# Inputbuffer_Equalizer.net
KiCad netlist of a schematic drawn in Altium Designer
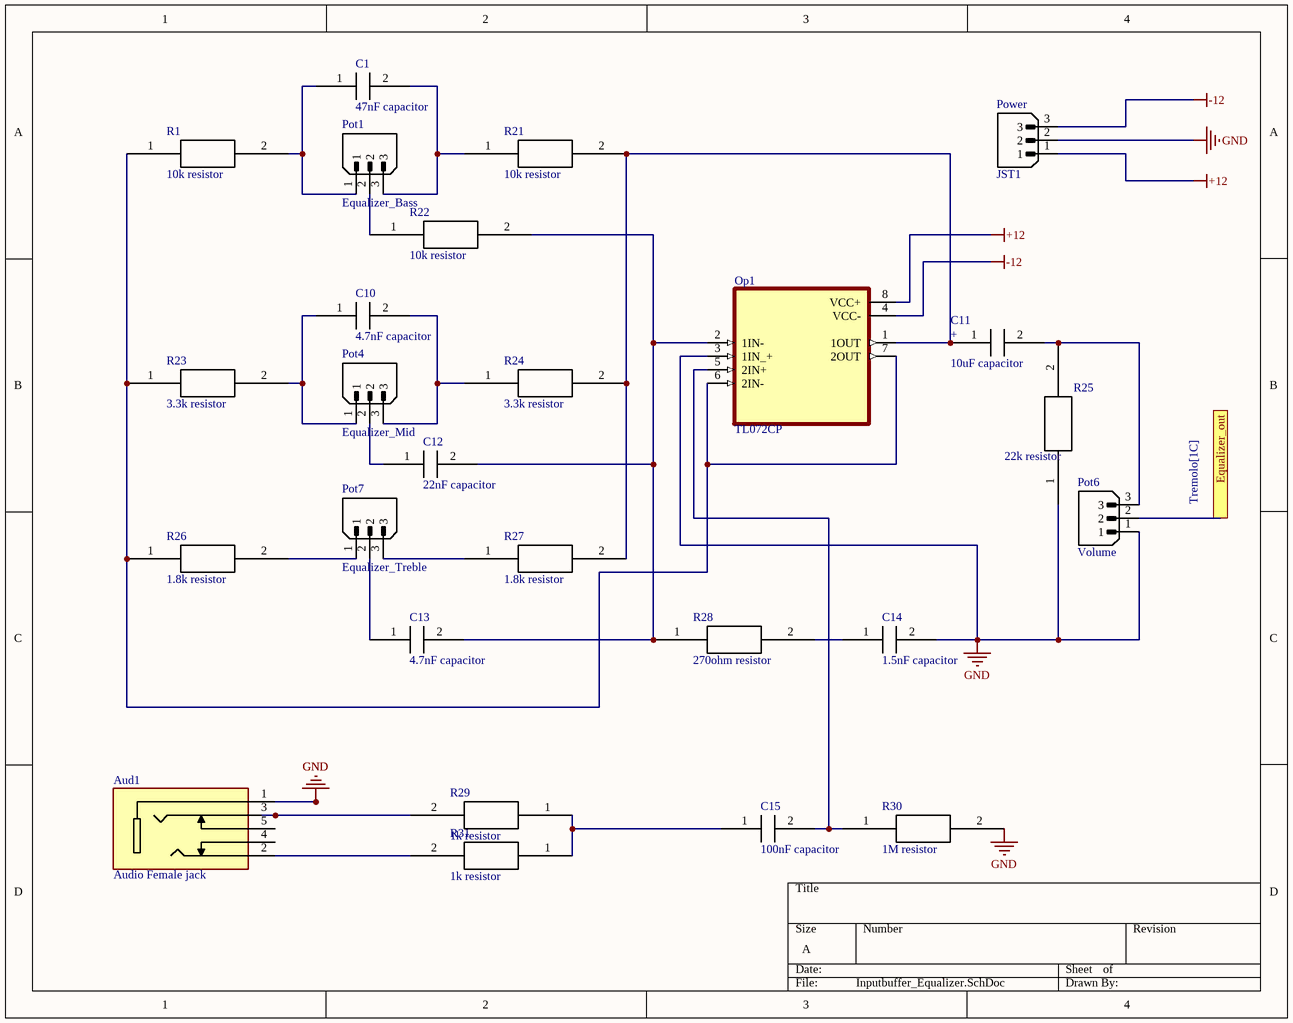
[diagram p0: Inputbuffer_Equalizer.SchDoc]

(export (version "E")
  (design (tool "Eeschema 10.0.6"))
  (components
    (comp (ref "Aud1")
      (value "Audio Female jack")
      (footprint "Audio Female Jack")
      (libsource (lib "Analog_Project_Schlib") (part "Audio Female jack"))
    )
    (comp (ref "C1")
      (value "47nF capacitor")
      (footprint "47nF")
      (libsource (lib "Analog_Project_Schlib") (part "47nF capacitor"))
    )
    (comp (ref "C10")
      (value "4.7nF capacitor")
      (footprint "4.7nF")
      (libsource (lib "Analog_Project_Schlib") (part "4.7nF capacitor"))
    )
    (comp (ref "C11")
      (value "10uF capacitor")
      (footprint "10uF")
      (libsource (lib "Analog_Project_Schlib") (part "10uF capacitor"))
    )
    (comp (ref "C12")
      (value "22nF capacitor")
      (footprint "22nF")
      (libsource (lib "Analog_Project_Schlib") (part "22nF capacitor"))
    )
    (comp (ref "C13")
      (value "4.7nF capacitor")
      (footprint "4.7nF")
      (libsource (lib "Analog_Project_Schlib") (part "4.7nF capacitor"))
    )
    (comp (ref "C14")
      (value "1.5nF capacitor")
      (footprint "1.5nF")
      (libsource (lib "Analog_Project_Schlib") (part "1.5nF capacitor"))
    )
    (comp (ref "C15")
      (value "100nF capacitor")
      (footprint "100nF")
      (libsource (lib "Analog_Project_Schlib") (part "100nF capacitor"))
    )
    (comp (ref "JST1")
      (value "Power")
      (footprint "3pin_jst")
      (libsource (lib "Analog_Project_Schlib") (part "3pin_jst"))
    )
    (comp (ref "Op1")
      (value "TL072CP")
      (footprint "TL072CP")
      (libsource (lib "Analog_Project_Schlib") (part "TL072CP"))
    )
    (comp (ref "Pot1")
      (value "Equalizer_Bass")
      (footprint "3pin_jst")
      (libsource (lib "") (part "3pin_jst_1"))
    )
    (comp (ref "Pot4")
      (value "Equalizer_Mid")
      (footprint "3pin_jst")
      (libsource (lib "") (part "3pin_jst_1"))
    )
    (comp (ref "Pot6")
      (value "Volume")
      (footprint "3pin_jst")
      (libsource (lib "Analog_Project_Schlib") (part "3pin_jst"))
    )
    (comp (ref "Pot7")
      (value "Equalizer_Treble")
      (footprint "3pin_jst")
      (libsource (lib "") (part "3pin_jst_1"))
    )
    (comp (ref "R1")
      (value "10k resistor")
      (footprint "10k")
      (libsource (lib "Analog_Project_Schlib") (part "10k resistor"))
    )
    (comp (ref "R21")
      (value "10k resistor")
      (footprint "10k")
      (libsource (lib "Analog_Project_Schlib") (part "10k resistor"))
    )
    (comp (ref "R22")
      (value "10k resistor")
      (footprint "10k")
      (libsource (lib "Analog_Project_Schlib") (part "10k resistor"))
    )
    (comp (ref "R23")
      (value "3.3k resistor")
      (footprint "3.3k")
      (libsource (lib "Analog_Project_Schlib") (part "3.3k resistor"))
    )
    (comp (ref "R24")
      (value "3.3k resistor")
      (footprint "3.3k")
      (libsource (lib "Analog_Project_Schlib") (part "3.3k resistor"))
    )
    (comp (ref "R25")
      (value "22k resistor")
      (footprint "22k")
      (libsource (lib "Analog_Project_Schlib") (part "22k resistor"))
    )
    (comp (ref "R26")
      (value "1.8k resistor")
      (footprint "1.8k")
      (libsource (lib "Analog_Project_Schlib") (part "1.8k resistor"))
    )
    (comp (ref "R27")
      (value "1.8k resistor")
      (footprint "1.8k")
      (libsource (lib "Analog_Project_Schlib") (part "1.8k resistor"))
    )
    (comp (ref "R28")
      (value "270ohm resistor")
      (footprint "270")
      (libsource (lib "Analog_Project_Schlib") (part "270ohm resistor"))
    )
    (comp (ref "R29")
      (value "1k resistor")
      (footprint "1k")
      (libsource (lib "Analog_Project_Schlib") (part "1k resistor"))
    )
    (comp (ref "R30")
      (value "1M resistor")
      (footprint "1M")
      (libsource (lib "Analog_Project_Schlib") (part "1M resistor"))
    )
    (comp (ref "R31")
      (value "1k resistor")
      (footprint "1k")
      (libsource (lib "Analog_Project_Schlib") (part "1k resistor"))
    )
  )
  (nets
    (net (code "1") (name "+12") (class "Default")
      (node (ref "JST1") (pin "1") (pinfunction "1_1") (pintype "passive"))
      (node (ref "Op1") (pin "8") (pinfunction "VCC+_8") (pintype "power_in"))
    )
    (net (code "2") (name "-12") (class "Default")
      (node (ref "JST1") (pin "3") (pinfunction "3_3") (pintype "passive"))
      (node (ref "Op1") (pin "4") (pinfunction "VCC-_4") (pintype "power_in"))
    )
    (net (code "3") (name "/Equalizer_out") (class "Default")
      (node (ref "Pot6") (pin "2") (pinfunction "2_2") (pintype "passive"))
    )
    (net (code "4") (name "GND") (class "Default")
      (node (ref "Aud1") (pin "1") (pinfunction "1_1") (pintype "passive"))
      (node (ref "C14") (pin "2") (pinfunction "2_2") (pintype "passive"))
      (node (ref "JST1") (pin "2") (pinfunction "2_2") (pintype "passive"))
      (node (ref "Op1") (pin "3") (pinfunction "1IN_+_3") (pintype "input"))
      (node (ref "Pot6") (pin "1") (pinfunction "1_1") (pintype "passive"))
      (node (ref "R25") (pin "1") (pinfunction "1_1") (pintype "passive"))
      (node (ref "R30") (pin "2") (pinfunction "2_2") (pintype "passive"))
    )
    (net (code "5") (name "Net-(Aud1-Pad2)") (class "Default")
      (node (ref "Aud1") (pin "2") (pinfunction "2_2") (pintype "passive"))
      (node (ref "R31") (pin "2") (pinfunction "2_2") (pintype "passive"))
    )
    (net (code "6") (name "Net-(Aud1-Pad3)") (class "Default")
      (node (ref "Aud1") (pin "3") (pinfunction "3_3") (pintype "passive"))
      (node (ref "R29") (pin "2") (pinfunction "2_2") (pintype "passive"))
    )
    (net (code "7") (name "Net-(C1-Pad1)") (class "Default")
      (node (ref "C1") (pin "1") (pinfunction "1_1") (pintype "passive"))
      (node (ref "Pot1") (pin "1") (pinfunction "1_1") (pintype "passive"))
      (node (ref "R1") (pin "2") (pinfunction "2_2") (pintype "passive"))
    )
    (net (code "8") (name "Net-(C1-Pad2)") (class "Default")
      (node (ref "C1") (pin "2") (pinfunction "2_2") (pintype "passive"))
      (node (ref "Pot1") (pin "3") (pinfunction "3_3") (pintype "passive"))
      (node (ref "R21") (pin "1") (pinfunction "1_1") (pintype "passive"))
    )
    (net (code "9") (name "Net-(C10-Pad1)") (class "Default")
      (node (ref "C10") (pin "1") (pinfunction "1_1") (pintype "passive"))
      (node (ref "Pot4") (pin "1") (pinfunction "1_1") (pintype "passive"))
      (node (ref "R23") (pin "2") (pinfunction "2_2") (pintype "passive"))
    )
    (net (code "10") (name "Net-(C10-Pad2)") (class "Default")
      (node (ref "C10") (pin "2") (pinfunction "2_2") (pintype "passive"))
      (node (ref "Pot4") (pin "3") (pinfunction "3_3") (pintype "passive"))
      (node (ref "R24") (pin "1") (pinfunction "1_1") (pintype "passive"))
    )
    (net (code "11") (name "Net-(C11-Pad2)") (class "Default")
      (node (ref "C11") (pin "2") (pinfunction "2_2") (pintype "passive"))
      (node (ref "Pot6") (pin "3") (pinfunction "3_3") (pintype "passive"))
      (node (ref "R25") (pin "2") (pinfunction "2_2") (pintype "passive"))
    )
    (net (code "12") (name "Net-(C12-Pad1)") (class "Default")
      (node (ref "C12") (pin "1") (pinfunction "1_1") (pintype "passive"))
      (node (ref "Pot4") (pin "2") (pinfunction "2_2") (pintype "passive"))
    )
    (net (code "13") (name "Net-(C12-_2)") (class "Default")
      (node (ref "C12") (pin "2") (pinfunction "_2_2") (pintype "passive"))
      (node (ref "C13") (pin "2") (pinfunction "2_2") (pintype "passive"))
      (node (ref "Op1") (pin "2") (pinfunction "1IN-_2") (pintype "input"))
      (node (ref "R22") (pin "2") (pinfunction "2_2") (pintype "passive"))
      (node (ref "R28") (pin "1") (pinfunction "1_1") (pintype "passive"))
    )
    (net (code "14") (name "Net-(C13-Pad1)") (class "Default")
      (node (ref "C13") (pin "1") (pinfunction "1_1") (pintype "passive"))
      (node (ref "Pot7") (pin "2") (pinfunction "2_2") (pintype "passive"))
    )
    (net (code "15") (name "Net-(C14-Pad1)") (class "Default")
      (node (ref "C14") (pin "1") (pinfunction "1_1") (pintype "passive"))
      (node (ref "R28") (pin "2") (pinfunction "2_2") (pintype "passive"))
    )
    (net (code "16") (name "Net-(C15-Pad1)") (class "Default")
      (node (ref "C15") (pin "1") (pinfunction "1_1") (pintype "passive"))
      (node (ref "R29") (pin "1") (pinfunction "1_1") (pintype "passive"))
      (node (ref "R31") (pin "1") (pinfunction "1_1") (pintype "passive"))
    )
    (net (code "17") (name "Net-(Op1-1OUT)") (class "Default")
      (node (ref "C11") (pin "1") (pinfunction "1_1") (pintype "passive"))
      (node (ref "Op1") (pin "1") (pinfunction "1OUT_1") (pintype "output"))
      (node (ref "R21") (pin "2") (pinfunction "2_2") (pintype "passive"))
      (node (ref "R24") (pin "2") (pinfunction "2_2") (pintype "passive"))
      (node (ref "R27") (pin "2") (pinfunction "2_2") (pintype "passive"))
    )
    (net (code "18") (name "Net-(Op1-2IN+)") (class "Default")
      (node (ref "C15") (pin "2") (pintype "passive"))
      (node (ref "Op1") (pin "5") (pinfunction "2IN+_5") (pintype "input"))
      (node (ref "R30") (pin "1") (pinfunction "1_1") (pintype "passive"))
    )
    (net (code "19") (name "Net-(Op1-2IN-)") (class "Default")
      (node (ref "Op1") (pin "6") (pinfunction "2IN-_6") (pintype "input"))
      (node (ref "Op1") (pin "7") (pinfunction "2OUT_7") (pintype "output"))
      (node (ref "R1") (pin "1") (pinfunction "1_1") (pintype "passive"))
      (node (ref "R23") (pin "1") (pinfunction "1_1") (pintype "passive"))
      (node (ref "R26") (pin "1") (pinfunction "1_1") (pintype "passive"))
    )
    (net (code "20") (name "Net-(Pot1-Pad2)") (class "Default")
      (node (ref "Pot1") (pin "2") (pinfunction "2_2") (pintype "passive"))
      (node (ref "R22") (pin "1") (pinfunction "1_1") (pintype "passive"))
    )
    (net (code "21") (name "Net-(Pot7-Pad1)") (class "Default")
      (node (ref "Pot7") (pin "1") (pinfunction "1_1") (pintype "passive"))
      (node (ref "R26") (pin "2") (pinfunction "2_2") (pintype "passive"))
    )
    (net (code "22") (name "Net-(Pot7-Pad3)") (class "Default")
      (node (ref "Pot7") (pin "3") (pinfunction "3_3") (pintype "passive"))
      (node (ref "R27") (pin "1") (pinfunction "1_1") (pintype "passive"))
    )
    (net (code "23") (name "unconnected-(Aud1-Pad4)") (class "Default")
      (node (ref "Aud1") (pin "4") (pinfunction "4_4") (pintype "passive"))
    )
    (net (code "24") (name "unconnected-(Aud1-Pad5)") (class "Default")
      (node (ref "Aud1") (pin "5") (pinfunction "5_5") (pintype "passive"))
    )
  )
)
